# RJW_VCA.net
KiCad netlist of a schematic drawn in EAGLE
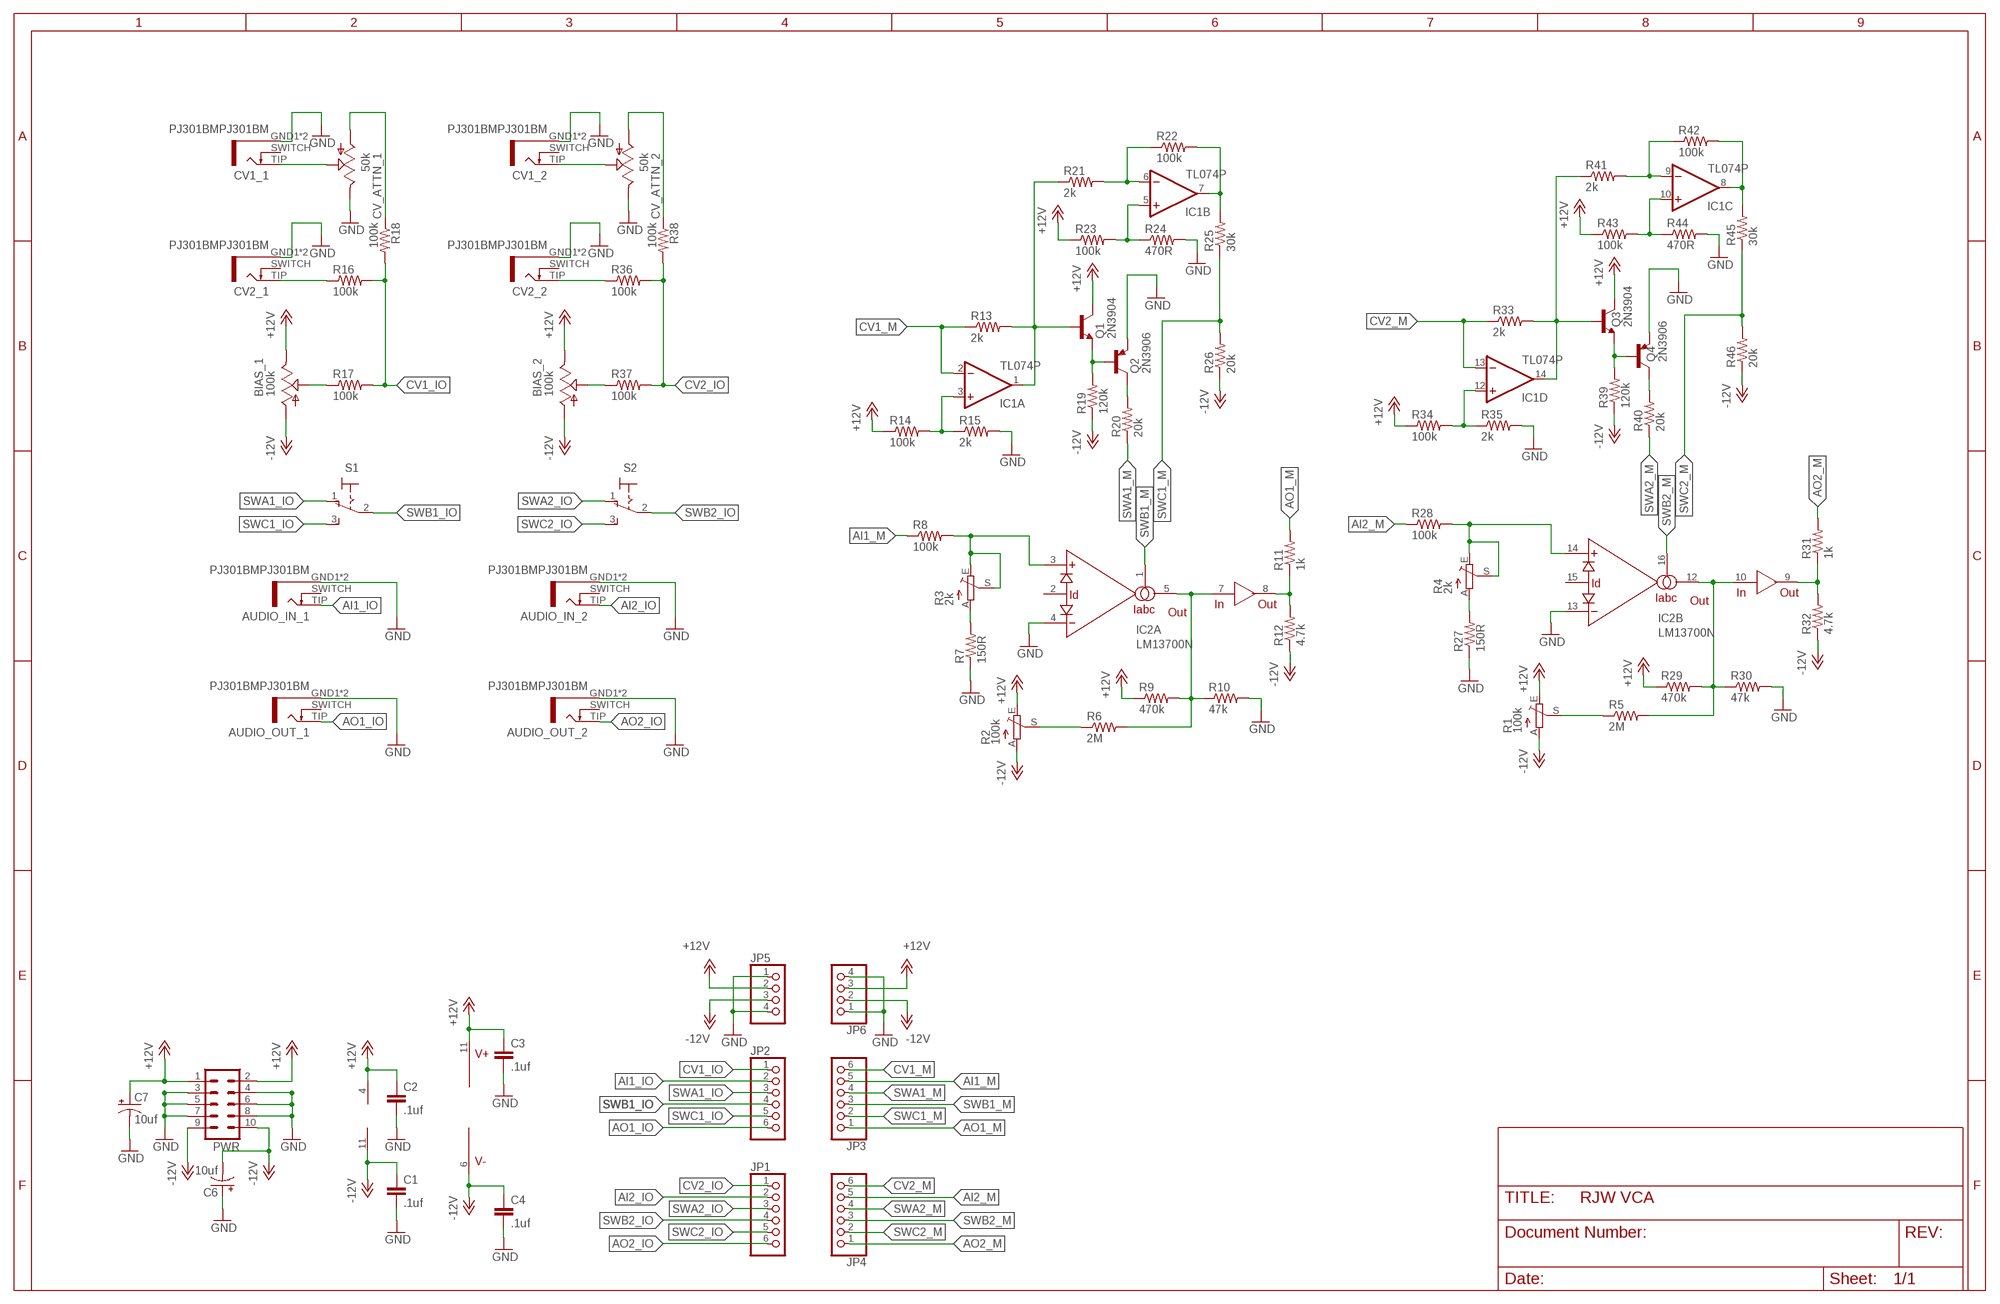
[diagram p0: schematic, sheet 1]

(export (version "E")
  (design (tool "Eeschema 10.0.6"))
  (components
    (comp (ref "AUDIO_IN_1")
      (value "PJ301BMPJ301BM")
      (footprint "eagle-import:PJ301BM")
      (libsource (lib "eagle-import") (part "PJ301BMPJ301BM"))
    )
    (comp (ref "AUDIO_IN_2")
      (value "PJ301BMPJ301BM")
      (footprint "eagle-import:PJ301BM")
      (libsource (lib "eagle-import") (part "PJ301BMPJ301BM"))
    )
    (comp (ref "AUDIO_OUT_1")
      (value "PJ301BMPJ301BM")
      (footprint "eagle-import:PJ301BM")
      (libsource (lib "eagle-import") (part "PJ301BMPJ301BM"))
    )
    (comp (ref "AUDIO_OUT_2")
      (value "PJ301BMPJ301BM")
      (footprint "eagle-import:PJ301BM")
      (libsource (lib "eagle-import") (part "PJ301BMPJ301BM"))
    )
    (comp (ref "BIAS_1")
      (value "100k")
      (footprint "eagle-import:EVUF")
      (libsource (lib "eagle-import") (part "ALPHA-9MMA"))
    )
    (comp (ref "BIAS_2")
      (value "100k")
      (footprint "eagle-import:EVUF")
      (libsource (lib "eagle-import") (part "ALPHA-9MMA"))
    )
    (comp (ref "C1")
      (value ".1uf")
      (footprint "eagle-import:C050-024X044")
      (libsource (lib "eagle-import") (part "C-EU050-024X044"))
    )
    (comp (ref "C2")
      (value ".1uf")
      (footprint "eagle-import:C050-024X044")
      (libsource (lib "eagle-import") (part "C-EU050-024X044"))
    )
    (comp (ref "C3")
      (value ".1uf")
      (footprint "eagle-import:C050-024X044")
      (libsource (lib "eagle-import") (part "C-EU050-024X044"))
    )
    (comp (ref "C4")
      (value ".1uf")
      (footprint "eagle-import:C050-024X044")
      (libsource (lib "eagle-import") (part "C-EU050-024X044"))
    )
    (comp (ref "C6")
      (value "10uf")
      (footprint "eagle-import:E2,5-5")
      (libsource (lib "eagle-import") (part "CPOL-USE2.5-5"))
    )
    (comp (ref "C7")
      (value "10uf")
      (footprint "eagle-import:E2,5-5")
      (libsource (lib "eagle-import") (part "CPOL-USE2.5-5"))
    )
    (comp (ref "CV1_1")
      (value "PJ301BMPJ301BM")
      (footprint "eagle-import:PJ301BM")
      (libsource (lib "eagle-import") (part "PJ301BMPJ301BM"))
    )
    (comp (ref "CV1_2")
      (value "PJ301BMPJ301BM")
      (footprint "eagle-import:PJ301BM")
      (libsource (lib "eagle-import") (part "PJ301BMPJ301BM"))
    )
    (comp (ref "CV2_1")
      (value "PJ301BMPJ301BM")
      (footprint "eagle-import:PJ301BM")
      (libsource (lib "eagle-import") (part "PJ301BMPJ301BM"))
    )
    (comp (ref "CV2_2")
      (value "PJ301BMPJ301BM")
      (footprint "eagle-import:PJ301BM")
      (libsource (lib "eagle-import") (part "PJ301BMPJ301BM"))
    )
    (comp (ref "CV_ATTN_1")
      (value "50k")
      (footprint "eagle-import:EVUF")
      (libsource (lib "eagle-import") (part "ALPHA-9MMA"))
    )
    (comp (ref "CV_ATTN_2")
      (value "50k")
      (footprint "eagle-import:EVUF")
      (libsource (lib "eagle-import") (part "ALPHA-9MMA"))
    )
    (comp (ref "IC1")
      (value "TL074P")
      (footprint "eagle-import:DIL14")
      (libsource (lib "eagle-import") (part "TL074P"))
    )
    (comp (ref "IC2")
      (value "LM13700N")
      (footprint "eagle-import:DIL16")
      (libsource (lib "eagle-import") (part "LM13700N"))
    )
    (comp (ref "JP1")
      (value "PINHD-1X6")
      (footprint "eagle-import:1X06")
      (libsource (lib "eagle-import") (part "PINHD-1X6"))
    )
    (comp (ref "JP2")
      (value "PINHD-1X6")
      (footprint "eagle-import:1X06")
      (libsource (lib "eagle-import") (part "PINHD-1X6"))
    )
    (comp (ref "JP3")
      (value "PINHD-1X6")
      (footprint "eagle-import:1X06")
      (libsource (lib "eagle-import") (part "PINHD-1X6"))
    )
    (comp (ref "JP4")
      (value "PINHD-1X6")
      (footprint "eagle-import:1X06")
      (libsource (lib "eagle-import") (part "PINHD-1X6"))
    )
    (comp (ref "JP5")
      (value "PINHD-1X4")
      (footprint "eagle-import:1X04")
      (libsource (lib "eagle-import") (part "PINHD-1X4"))
    )
    (comp (ref "JP6")
      (value "PINHD-1X4")
      (footprint "eagle-import:1X04")
      (libsource (lib "eagle-import") (part "PINHD-1X4"))
    )
    (comp (ref "PWR")
      (value "ML10")
      (footprint "eagle-import:ML10")
      (libsource (lib "eagle-import") (part "ML10"))
    )
    (comp (ref "Q1")
      (value "2N3904")
      (footprint "eagle-import:TO92")
      (libsource (lib "eagle-import") (part "2N3904"))
    )
    (comp (ref "Q2")
      (value "2N3906")
      (footprint "eagle-import:TO92")
      (libsource (lib "eagle-import") (part "2N3906"))
    )
    (comp (ref "Q3")
      (value "2N3904")
      (footprint "eagle-import:TO92")
      (libsource (lib "eagle-import") (part "2N3904"))
    )
    (comp (ref "Q4")
      (value "2N3906")
      (footprint "eagle-import:TO92")
      (libsource (lib "eagle-import") (part "2N3906"))
    )
    (comp (ref "R1")
      (value "100k")
      (footprint "eagle-import:S64YW")
      (libsource (lib "eagle-import") (part "TRIM_1234-S64YW"))
    )
    (comp (ref "R2")
      (value "100k")
      (footprint "eagle-import:S64YW")
      (libsource (lib "eagle-import") (part "TRIM_1234-S64YW"))
    )
    (comp (ref "R3")
      (value "2k")
      (footprint "eagle-import:S64YW")
      (libsource (lib "eagle-import") (part "TRIM_1234-S64YW"))
    )
    (comp (ref "R4")
      (value "2k")
      (footprint "eagle-import:S64YW")
      (libsource (lib "eagle-import") (part "TRIM_1234-S64YW"))
    )
    (comp (ref "R5")
      (value "2M")
      (footprint "eagle-import:0204_7")
      (libsource (lib "eagle-import") (part "R-US_0204/7"))
    )
    (comp (ref "R6")
      (value "2M")
      (footprint "eagle-import:0204_7")
      (libsource (lib "eagle-import") (part "R-US_0204/7"))
    )
    (comp (ref "R7")
      (value "150R")
      (footprint "eagle-import:0204_7")
      (libsource (lib "eagle-import") (part "R-US_0204/7"))
    )
    (comp (ref "R8")
      (value "100k")
      (footprint "eagle-import:0204_7")
      (libsource (lib "eagle-import") (part "R-US_0204/7"))
    )
    (comp (ref "R9")
      (value "470k")
      (footprint "eagle-import:0204_7")
      (libsource (lib "eagle-import") (part "R-US_0204/7"))
    )
    (comp (ref "R10")
      (value "47k")
      (footprint "eagle-import:0204_7")
      (libsource (lib "eagle-import") (part "R-US_0204/7"))
    )
    (comp (ref "R11")
      (value "1k")
      (footprint "eagle-import:0204_7")
      (libsource (lib "eagle-import") (part "R-US_0204/7"))
    )
    (comp (ref "R12")
      (value "4.7k")
      (footprint "eagle-import:0204_7")
      (libsource (lib "eagle-import") (part "R-US_0204/7"))
    )
    (comp (ref "R13")
      (value "2k")
      (footprint "eagle-import:0204_7")
      (libsource (lib "eagle-import") (part "R-US_0204/7"))
    )
    (comp (ref "R14")
      (value "100k")
      (footprint "eagle-import:0204_7")
      (libsource (lib "eagle-import") (part "R-US_0204/7"))
    )
    (comp (ref "R15")
      (value "2k")
      (footprint "eagle-import:0204_7")
      (libsource (lib "eagle-import") (part "R-US_0204/7"))
    )
    (comp (ref "R16")
      (value "100k")
      (footprint "eagle-import:0204_7")
      (libsource (lib "eagle-import") (part "R-US_0204/7"))
    )
    (comp (ref "R17")
      (value "100k")
      (footprint "eagle-import:0204_7")
      (libsource (lib "eagle-import") (part "R-US_0204/7"))
    )
    (comp (ref "R18")
      (value "100k")
      (footprint "eagle-import:0204_7")
      (libsource (lib "eagle-import") (part "R-US_0204/7"))
    )
    (comp (ref "R19")
      (value "120k")
      (footprint "eagle-import:0204_7")
      (libsource (lib "eagle-import") (part "R-US_0204/7"))
    )
    (comp (ref "R20")
      (value "20k")
      (footprint "eagle-import:0204_7")
      (libsource (lib "eagle-import") (part "R-US_0204/7"))
    )
    (comp (ref "R21")
      (value "2k")
      (footprint "eagle-import:0204_7")
      (libsource (lib "eagle-import") (part "R-US_0204/7"))
    )
    (comp (ref "R22")
      (value "100k")
      (footprint "eagle-import:0204_7")
      (libsource (lib "eagle-import") (part "R-US_0204/7"))
    )
    (comp (ref "R23")
      (value "100k")
      (footprint "eagle-import:0204_7")
      (libsource (lib "eagle-import") (part "R-US_0204/7"))
    )
    (comp (ref "R24")
      (value "470R")
      (footprint "eagle-import:0204_7")
      (libsource (lib "eagle-import") (part "R-US_0204/7"))
    )
    (comp (ref "R25")
      (value "30k")
      (footprint "eagle-import:0204_7")
      (libsource (lib "eagle-import") (part "R-US_0204/7"))
    )
    (comp (ref "R26")
      (value "20k")
      (footprint "eagle-import:0204_7")
      (libsource (lib "eagle-import") (part "R-US_0204/7"))
    )
    (comp (ref "R27")
      (value "150R")
      (footprint "eagle-import:0204_7")
      (libsource (lib "eagle-import") (part "R-US_0204/7"))
    )
    (comp (ref "R28")
      (value "100k")
      (footprint "eagle-import:0204_7")
      (libsource (lib "eagle-import") (part "R-US_0204/7"))
    )
    (comp (ref "R29")
      (value "470k")
      (footprint "eagle-import:0204_7")
      (libsource (lib "eagle-import") (part "R-US_0204/7"))
    )
    (comp (ref "R30")
      (value "47k")
      (footprint "eagle-import:0204_7")
      (libsource (lib "eagle-import") (part "R-US_0204/7"))
    )
    (comp (ref "R31")
      (value "1k")
      (footprint "eagle-import:0204_7")
      (libsource (lib "eagle-import") (part "R-US_0204/7"))
    )
    (comp (ref "R32")
      (value "4.7k")
      (footprint "eagle-import:0204_7")
      (libsource (lib "eagle-import") (part "R-US_0204/7"))
    )
    (comp (ref "R33")
      (value "2k")
      (footprint "eagle-import:0204_7")
      (libsource (lib "eagle-import") (part "R-US_0204/7"))
    )
    (comp (ref "R34")
      (value "100k")
      (footprint "eagle-import:0204_7")
      (libsource (lib "eagle-import") (part "R-US_0204/7"))
    )
    (comp (ref "R35")
      (value "2k")
      (footprint "eagle-import:0204_7")
      (libsource (lib "eagle-import") (part "R-US_0204/7"))
    )
    (comp (ref "R36")
      (value "100k")
      (footprint "eagle-import:0204_7")
      (libsource (lib "eagle-import") (part "R-US_0204/7"))
    )
    (comp (ref "R37")
      (value "100k")
      (footprint "eagle-import:0204_7")
      (libsource (lib "eagle-import") (part "R-US_0204/7"))
    )
    (comp (ref "R38")
      (value "100k")
      (footprint "eagle-import:0204_7")
      (libsource (lib "eagle-import") (part "R-US_0204/7"))
    )
    (comp (ref "R39")
      (value "120k")
      (footprint "eagle-import:0204_7")
      (libsource (lib "eagle-import") (part "R-US_0204/7"))
    )
    (comp (ref "R40")
      (value "20k")
      (footprint "eagle-import:0204_7")
      (libsource (lib "eagle-import") (part "R-US_0204/7"))
    )
    (comp (ref "R41")
      (value "2k")
      (footprint "eagle-import:0204_7")
      (libsource (lib "eagle-import") (part "R-US_0204/7"))
    )
    (comp (ref "R42")
      (value "100k")
      (footprint "eagle-import:0204_7")
      (libsource (lib "eagle-import") (part "R-US_0204/7"))
    )
    (comp (ref "R43")
      (value "100k")
      (footprint "eagle-import:0204_7")
      (libsource (lib "eagle-import") (part "R-US_0204/7"))
    )
    (comp (ref "R44")
      (value "470R")
      (footprint "eagle-import:0204_7")
      (libsource (lib "eagle-import") (part "R-US_0204/7"))
    )
    (comp (ref "R45")
      (value "30k")
      (footprint "eagle-import:0204_7")
      (libsource (lib "eagle-import") (part "R-US_0204/7"))
    )
    (comp (ref "R46")
      (value "20k")
      (footprint "eagle-import:0204_7")
      (libsource (lib "eagle-import") (part "R-US_0204/7"))
    )
    (comp (ref "S1")
      (value "M9040P")
      (footprint "eagle-import:M9040P")
      (libsource (lib "eagle-import") (part "M9040P"))
    )
    (comp (ref "S2")
      (value "M9040P")
      (footprint "eagle-import:M9040P")
      (libsource (lib "eagle-import") (part "M9040P"))
    )
  )
  (nets
    (net (code "1") (name "+12V") (class "Default")
      (node (ref "BIAS_1") (pin "3") (pinfunction "E_3") (pintype "passive"))
      (node (ref "BIAS_2") (pin "3") (pinfunction "E_3") (pintype "passive"))
      (node (ref "C2") (pin "1") (pinfunction "1_1") (pintype "passive"))
      (node (ref "C3") (pin "1") (pinfunction "1_1") (pintype "passive"))
      (node (ref "C7") (pin "+") (pinfunction "+_+") (pintype "passive"))
      (node (ref "IC1") (pin "4") (pinfunction "V+_4") (pintype "power_in"))
      (node (ref "IC2") (pin "11") (pinfunction "V+_11") (pintype "bidirectional"))
      (node (ref "JP5") (pin "2") (pinfunction "2_2") (pintype "passive"))
      (node (ref "JP6") (pin "3") (pinfunction "3_3") (pintype "passive"))
      (node (ref "PWR") (pin "1") (pinfunction "1_1") (pintype "passive"))
      (node (ref "PWR") (pin "2") (pinfunction "2_2") (pintype "passive"))
      (node (ref "Q1") (pin "1") (pinfunction "C_1") (pintype "passive"))
      (node (ref "Q3") (pin "1") (pinfunction "C_1") (pintype "passive"))
      (node (ref "R1") (pin "E") (pinfunction "E_E") (pintype "passive"))
      (node (ref "R14") (pin "1") (pinfunction "1_1") (pintype "passive"))
      (node (ref "R2") (pin "E") (pinfunction "E_E") (pintype "passive"))
      (node (ref "R23") (pin "1") (pinfunction "1_1") (pintype "passive"))
      (node (ref "R29") (pin "1") (pinfunction "1_1") (pintype "passive"))
      (node (ref "R34") (pin "1") (pinfunction "1_1") (pintype "passive"))
      (node (ref "R43") (pin "1") (pinfunction "1_1") (pintype "passive"))
      (node (ref "R9") (pin "1") (pinfunction "1_1") (pintype "passive"))
    )
    (net (code "2") (name "-12V") (class "Default")
      (node (ref "BIAS_1") (pin "1") (pinfunction "A_1") (pintype "passive"))
      (node (ref "BIAS_2") (pin "1") (pinfunction "A_1") (pintype "passive"))
      (node (ref "C1") (pin "1") (pinfunction "1_1") (pintype "passive"))
      (node (ref "C4") (pin "1") (pinfunction "1_1") (pintype "passive"))
      (node (ref "C6") (pin "-") (pinfunction "-_-") (pintype "passive"))
      (node (ref "IC1") (pin "11") (pinfunction "V-_11") (pintype "power_in"))
      (node (ref "IC2") (pin "6") (pinfunction "V-_6") (pintype "bidirectional"))
      (node (ref "JP5") (pin "3") (pinfunction "3_3") (pintype "passive"))
      (node (ref "JP6") (pin "2") (pinfunction "2_2") (pintype "passive"))
      (node (ref "PWR") (pin "10") (pinfunction "10_10") (pintype "passive"))
      (node (ref "PWR") (pin "9") (pinfunction "9_9") (pintype "passive"))
      (node (ref "R1") (pin "A") (pinfunction "A_A") (pintype "passive"))
      (node (ref "R12") (pin "1") (pinfunction "1_1") (pintype "passive"))
      (node (ref "R19") (pin "1") (pinfunction "1_1") (pintype "passive"))
      (node (ref "R2") (pin "A") (pinfunction "A_A") (pintype "passive"))
      (node (ref "R26") (pin "1") (pinfunction "1_1") (pintype "passive"))
      (node (ref "R32") (pin "1") (pinfunction "1_1") (pintype "passive"))
      (node (ref "R39") (pin "1") (pinfunction "1_1") (pintype "passive"))
      (node (ref "R46") (pin "1") (pinfunction "1_1") (pintype "passive"))
    )
    (net (code "3") (name "AI1_IO") (class "Default")
      (node (ref "AUDIO_IN_1") (pin "TIP") (pinfunction "3_TIP") (pintype "passive"))
      (node (ref "JP2") (pin "2") (pinfunction "2_2") (pintype "passive"))
    )
    (net (code "4") (name "AI1_M") (class "Default")
      (node (ref "JP3") (pin "5") (pinfunction "5_5") (pintype "passive"))
      (node (ref "R8") (pin "1") (pinfunction "1_1") (pintype "passive"))
    )
    (net (code "5") (name "AI2_IO") (class "Default")
      (node (ref "AUDIO_IN_2") (pin "TIP") (pinfunction "3_TIP") (pintype "passive"))
      (node (ref "JP1") (pin "2") (pinfunction "2_2") (pintype "passive"))
    )
    (net (code "6") (name "AI2_M") (class "Default")
      (node (ref "JP4") (pin "5") (pinfunction "5_5") (pintype "passive"))
      (node (ref "R28") (pin "1") (pinfunction "1_1") (pintype "passive"))
    )
    (net (code "7") (name "AO1_IO") (class "Default")
      (node (ref "AUDIO_OUT_1") (pin "TIP") (pinfunction "3_TIP") (pintype "passive"))
      (node (ref "JP2") (pin "6") (pinfunction "6_6") (pintype "passive"))
    )
    (net (code "8") (name "AO1_M") (class "Default")
      (node (ref "JP3") (pin "1") (pinfunction "1_1") (pintype "passive"))
      (node (ref "R11") (pin "2") (pinfunction "2_2") (pintype "passive"))
    )
    (net (code "9") (name "AO2_IO") (class "Default")
      (node (ref "AUDIO_OUT_2") (pin "TIP") (pinfunction "3_TIP") (pintype "passive"))
      (node (ref "JP1") (pin "6") (pinfunction "6_6") (pintype "passive"))
    )
    (net (code "10") (name "AO2_M") (class "Default")
      (node (ref "JP4") (pin "1") (pinfunction "1_1") (pintype "passive"))
      (node (ref "R31") (pin "2") (pinfunction "2_2") (pintype "passive"))
    )
    (net (code "11") (name "CV1_IO") (class "Default")
      (node (ref "JP2") (pin "1") (pinfunction "1_1") (pintype "passive"))
      (node (ref "R16") (pin "2") (pinfunction "2_2") (pintype "passive"))
      (node (ref "R17") (pin "2") (pinfunction "2_2") (pintype "passive"))
      (node (ref "R18") (pin "2") (pinfunction "2_2") (pintype "passive"))
    )
    (net (code "12") (name "CV1_M") (class "Default")
      (node (ref "IC1") (pin "2") (pinfunction "-IN_2") (pintype "input"))
      (node (ref "JP3") (pin "6") (pinfunction "6_6") (pintype "passive"))
      (node (ref "R13") (pin "1") (pinfunction "1_1") (pintype "passive"))
    )
    (net (code "13") (name "CV2_IO") (class "Default")
      (node (ref "JP1") (pin "1") (pinfunction "1_1") (pintype "passive"))
      (node (ref "R36") (pin "2") (pinfunction "2_2") (pintype "passive"))
      (node (ref "R37") (pin "2") (pinfunction "2_2") (pintype "passive"))
      (node (ref "R38") (pin "2") (pinfunction "2_2") (pintype "passive"))
    )
    (net (code "14") (name "CV2_M") (class "Default")
      (node (ref "IC1") (pin "13") (pinfunction "-IN_13") (pintype "input"))
      (node (ref "JP4") (pin "6") (pinfunction "6_6") (pintype "passive"))
      (node (ref "R33") (pin "1") (pinfunction "1_1") (pintype "passive"))
    )
    (net (code "15") (name "GND") (class "Default")
      (node (ref "AUDIO_IN_1") (pin "GND1") (pinfunction "5_GND1") (pintype "passive"))
      (node (ref "AUDIO_IN_1") (pin "GND2") (pinfunction "5_GND2") (pintype "passive"))
      (node (ref "AUDIO_IN_2") (pin "GND1") (pinfunction "5_GND1") (pintype "passive"))
      (node (ref "AUDIO_IN_2") (pin "GND2") (pinfunction "5_GND2") (pintype "passive"))
      (node (ref "AUDIO_OUT_1") (pin "GND1") (pinfunction "5_GND1") (pintype "passive"))
      (node (ref "AUDIO_OUT_1") (pin "GND2") (pinfunction "5_GND2") (pintype "passive"))
      (node (ref "AUDIO_OUT_2") (pin "GND1") (pinfunction "5_GND1") (pintype "passive"))
      (node (ref "AUDIO_OUT_2") (pin "GND2") (pinfunction "5_GND2") (pintype "passive"))
      (node (ref "C1") (pin "2") (pinfunction "2_2") (pintype "passive"))
      (node (ref "C2") (pin "2") (pinfunction "2_2") (pintype "passive"))
      (node (ref "C3") (pin "2") (pinfunction "2_2") (pintype "passive"))
      (node (ref "C4") (pin "2") (pinfunction "2_2") (pintype "passive"))
      (node (ref "C6") (pin "+") (pinfunction "+_+") (pintype "passive"))
      (node (ref "C7") (pin "-") (pinfunction "-_-") (pintype "passive"))
      (node (ref "CV1_1") (pin "GND1") (pinfunction "5_GND1") (pintype "passive"))
      (node (ref "CV1_1") (pin "GND2") (pinfunction "5_GND2") (pintype "passive"))
      (node (ref "CV1_2") (pin "GND1") (pinfunction "5_GND1") (pintype "passive"))
      (node (ref "CV1_2") (pin "GND2") (pinfunction "5_GND2") (pintype "passive"))
      (node (ref "CV2_1") (pin "GND1") (pinfunction "5_GND1") (pintype "passive"))
      (node (ref "CV2_1") (pin "GND2") (pinfunction "5_GND2") (pintype "passive"))
      (node (ref "CV2_2") (pin "GND1") (pinfunction "5_GND1") (pintype "passive"))
      (node (ref "CV2_2") (pin "GND2") (pinfunction "5_GND2") (pintype "passive"))
      (node (ref "CV_ATTN_1") (pin "3") (pinfunction "E_3") (pintype "passive"))
      (node (ref "CV_ATTN_2") (pin "3") (pinfunction "E_3") (pintype "passive"))
      (node (ref "IC2") (pin "13") (pinfunction "-IN_13") (pintype "bidirectional"))
      (node (ref "IC2") (pin "4") (pinfunction "-IN_4") (pintype "bidirectional"))
      (node (ref "JP5") (pin "1") (pinfunction "1_1") (pintype "passive"))
      (node (ref "JP5") (pin "4") (pinfunction "4_4") (pintype "passive"))
      (node (ref "JP6") (pin "1") (pinfunction "1_1") (pintype "passive"))
      (node (ref "JP6") (pin "4") (pinfunction "4_4") (pintype "passive"))
      (node (ref "PWR") (pin "3") (pinfunction "3_3") (pintype "passive"))
      (node (ref "PWR") (pin "4") (pinfunction "4_4") (pintype "passive"))
      (node (ref "PWR") (pin "5") (pinfunction "5_5") (pintype "passive"))
      (node (ref "PWR") (pin "6") (pinfunction "6_6") (pintype "passive"))
      (node (ref "PWR") (pin "7") (pinfunction "7_7") (pintype "passive"))
      (node (ref "PWR") (pin "8") (pinfunction "8_8") (pintype "passive"))
      (node (ref "Q2") (pin "3") (pinfunction "E_3") (pintype "passive"))
      (node (ref "Q4") (pin "3") (pinfunction "E_3") (pintype "passive"))
      (node (ref "R10") (pin "2") (pinfunction "2_2") (pintype "passive"))
      (node (ref "R15") (pin "2") (pinfunction "2_2") (pintype "passive"))
      (node (ref "R24") (pin "2") (pinfunction "2_2") (pintype "passive"))
      (node (ref "R27") (pin "1") (pinfunction "1_1") (pintype "passive"))
      (node (ref "R30") (pin "2") (pinfunction "2_2") (pintype "passive"))
      (node (ref "R35") (pin "2") (pinfunction "2_2") (pintype "passive"))
      (node (ref "R44") (pin "2") (pinfunction "2_2") (pintype "passive"))
      (node (ref "R7") (pin "1") (pinfunction "1_1") (pintype "passive"))
    )
    (net (code "16") (name "Net-(BIAS_1-S)") (class "Default")
      (node (ref "BIAS_1") (pin "2") (pinfunction "S_2") (pintype "passive"))
      (node (ref "R17") (pin "1") (pinfunction "1_1") (pintype "passive"))
    )
    (net (code "17") (name "Net-(BIAS_2-S)") (class "Default")
      (node (ref "BIAS_2") (pin "2") (pinfunction "S_2") (pintype "passive"))
      (node (ref "R37") (pin "1") (pinfunction "1_1") (pintype "passive"))
    )
    (net (code "18") (name "Net-(CV1_1-3)") (class "Default")
      (node (ref "CV1_1") (pin "TIP") (pinfunction "3_TIP") (pintype "passive"))
      (node (ref "CV_ATTN_1") (pin "2") (pinfunction "S_2") (pintype "passive"))
    )
    (net (code "19") (name "Net-(CV1_2-3)") (class "Default")
      (node (ref "CV1_2") (pin "TIP") (pinfunction "3_TIP") (pintype "passive"))
      (node (ref "CV_ATTN_2") (pin "2") (pinfunction "S_2") (pintype "passive"))
    )
    (net (code "20") (name "Net-(CV2_1-3)") (class "Default")
      (node (ref "CV2_1") (pin "TIP") (pinfunction "3_TIP") (pintype "passive"))
      (node (ref "R16") (pin "1") (pinfunction "1_1") (pintype "passive"))
    )
    (net (code "21") (name "Net-(CV2_2-3)") (class "Default")
      (node (ref "CV2_2") (pin "TIP") (pinfunction "3_TIP") (pintype "passive"))
      (node (ref "R36") (pin "1") (pinfunction "1_1") (pintype "passive"))
    )
    (net (code "22") (name "Net-(CV_ATTN_1-A)") (class "Default")
      (node (ref "CV_ATTN_1") (pin "1") (pinfunction "A_1") (pintype "passive"))
      (node (ref "R18") (pin "1") (pinfunction "1_1") (pintype "passive"))
    )
    (net (code "23") (name "Net-(CV_ATTN_2-A)") (class "Default")
      (node (ref "CV_ATTN_2") (pin "1") (pinfunction "A_1") (pintype "passive"))
      (node (ref "R38") (pin "1") (pinfunction "1_1") (pintype "passive"))
    )
    (net (code "24") (name "Net-(IC1A-+IN)") (class "Default")
      (node (ref "IC1") (pin "3") (pinfunction "+IN_3") (pintype "input"))
      (node (ref "R14") (pin "2") (pinfunction "2_2") (pintype "passive"))
      (node (ref "R15") (pin "1") (pinfunction "1_1") (pintype "passive"))
    )
    (net (code "25") (name "Net-(IC1A-OUT)") (class "Default")
      (node (ref "IC1") (pin "1") (pinfunction "OUT_1") (pintype "output"))
      (node (ref "Q1") (pin "2") (pinfunction "B_2") (pintype "passive"))
      (node (ref "R13") (pin "2") (pinfunction "2_2") (pintype "passive"))
      (node (ref "R21") (pin "1") (pinfunction "1_1") (pintype "passive"))
    )
    (net (code "26") (name "Net-(IC1B-+IN)") (class "Default")
      (node (ref "IC1") (pin "5") (pinfunction "+IN_5") (pintype "input"))
      (node (ref "R23") (pin "2") (pinfunction "2_2") (pintype "passive"))
      (node (ref "R24") (pin "1") (pinfunction "1_1") (pintype "passive"))
    )
    (net (code "27") (name "Net-(IC1B--IN)") (class "Default")
      (node (ref "IC1") (pin "6") (pinfunction "-IN_6") (pintype "input"))
      (node (ref "R21") (pin "2") (pinfunction "2_2") (pintype "passive"))
      (node (ref "R22") (pin "1") (pinfunction "1_1") (pintype "passive"))
    )
    (net (code "28") (name "Net-(IC1B-OUT)") (class "Default")
      (node (ref "IC1") (pin "7") (pinfunction "OUT_7") (pintype "output"))
      (node (ref "R22") (pin "2") (pinfunction "2_2") (pintype "passive"))
      (node (ref "R25") (pin "2") (pinfunction "2_2") (pintype "passive"))
    )
    (net (code "29") (name "Net-(IC1C-+IN)") (class "Default")
      (node (ref "IC1") (pin "10") (pinfunction "+IN_10") (pintype "input"))
      (node (ref "R43") (pin "2") (pinfunction "2_2") (pintype "passive"))
      (node (ref "R44") (pin "1") (pinfunction "1_1") (pintype "passive"))
    )
    (net (code "30") (name "Net-(IC1C--IN)") (class "Default")
      (node (ref "IC1") (pin "9") (pinfunction "-IN_9") (pintype "input"))
      (node (ref "R41") (pin "2") (pinfunction "2_2") (pintype "passive"))
      (node (ref "R42") (pin "1") (pinfunction "1_1") (pintype "passive"))
    )
    (net (code "31") (name "Net-(IC1C-OUT)") (class "Default")
      (node (ref "IC1") (pin "8") (pinfunction "OUT_8") (pintype "output"))
      (node (ref "R42") (pin "2") (pinfunction "2_2") (pintype "passive"))
      (node (ref "R45") (pin "2") (pinfunction "2_2") (pintype "passive"))
    )
    (net (code "32") (name "Net-(IC1D-+IN)") (class "Default")
      (node (ref "IC1") (pin "12") (pinfunction "+IN_12") (pintype "input"))
      (node (ref "R34") (pin "2") (pinfunction "2_2") (pintype "passive"))
      (node (ref "R35") (pin "1") (pinfunction "1_1") (pintype "passive"))
    )
    (net (code "33") (name "Net-(IC1D-OUT)") (class "Default")
      (node (ref "IC1") (pin "14") (pinfunction "OUT_14") (pintype "output"))
      (node (ref "Q3") (pin "2") (pinfunction "B_2") (pintype "passive"))
      (node (ref "R33") (pin "2") (pinfunction "2_2") (pintype "passive"))
      (node (ref "R41") (pin "1") (pinfunction "1_1") (pintype "passive"))
    )
    (net (code "34") (name "Net-(IC2A-+IN)") (class "Default")
      (node (ref "IC2") (pin "3") (pinfunction "+IN_3") (pintype "bidirectional"))
      (node (ref "R3") (pin "E") (pinfunction "E_E") (pintype "passive"))
      (node (ref "R3") (pin "S") (pinfunction "S_S") (pintype "passive"))
      (node (ref "R8") (pin "2") (pinfunction "2_2") (pintype "passive"))
    )
    (net (code "35") (name "Net-(IC2A-OUT)") (class "Default")
      (node (ref "IC2") (pin "5") (pinfunction "OUT_5") (pintype "bidirectional"))
      (node (ref "IC2") (pin "7") (pinfunction "IN_7") (pintype "bidirectional"))
      (node (ref "R10") (pin "1") (pinfunction "1_1") (pintype "passive"))
      (node (ref "R6") (pin "2") (pinfunction "2_2") (pintype "passive"))
      (node (ref "R9") (pin "2") (pinfunction "2_2") (pintype "passive"))
    )
    (net (code "36") (name "Net-(IC2B-+IN)") (class "Default")
      (node (ref "IC2") (pin "14") (pinfunction "+IN_14") (pintype "bidirectional"))
      (node (ref "R28") (pin "2") (pinfunction "2_2") (pintype "passive"))
      (node (ref "R4") (pin "E") (pinfunction "E_E") (pintype "passive"))
      (node (ref "R4") (pin "S") (pinfunction "S_S") (pintype "passive"))
    )
    (net (code "37") (name "Net-(IC2B-OUT)") (class "Default")
      (node (ref "IC2") (pin "10") (pinfunction "IN_10") (pintype "bidirectional"))
      (node (ref "IC2") (pin "12") (pinfunction "OUT_12") (pintype "bidirectional"))
      (node (ref "R29") (pin "2") (pinfunction "2_2") (pintype "passive"))
      (node (ref "R30") (pin "1") (pinfunction "1_1") (pintype "passive"))
      (node (ref "R5") (pin "2") (pinfunction "2_2") (pintype "passive"))
    )
    (net (code "38") (name "Net-(IC2C-OUT)") (class "Default")
      (node (ref "IC2") (pin "8") (pinfunction "OUT_8") (pintype "bidirectional"))
      (node (ref "R11") (pin "1") (pinfunction "1_1") (pintype "passive"))
      (node (ref "R12") (pin "2") (pinfunction "2_2") (pintype "passive"))
    )
    (net (code "39") (name "Net-(IC2D-OUT)") (class "Default")
      (node (ref "IC2") (pin "9") (pinfunction "OUT_9") (pintype "bidirectional"))
      (node (ref "R31") (pin "1") (pinfunction "1_1") (pintype "passive"))
      (node (ref "R32") (pin "2") (pinfunction "2_2") (pintype "passive"))
    )
    (net (code "40") (name "Net-(Q1-E)") (class "Default")
      (node (ref "Q1") (pin "3") (pinfunction "E_3") (pintype "passive"))
      (node (ref "Q2") (pin "2") (pinfunction "B_2") (pintype "passive"))
      (node (ref "R19") (pin "2") (pinfunction "2_2") (pintype "passive"))
    )
    (net (code "41") (name "Net-(Q2-C)") (class "Default")
      (node (ref "Q2") (pin "1") (pinfunction "C_1") (pintype "passive"))
      (node (ref "R20") (pin "2") (pinfunction "2_2") (pintype "passive"))
    )
    (net (code "42") (name "Net-(Q3-E)") (class "Default")
      (node (ref "Q3") (pin "3") (pinfunction "E_3") (pintype "passive"))
      (node (ref "Q4") (pin "2") (pinfunction "B_2") (pintype "passive"))
      (node (ref "R39") (pin "2") (pinfunction "2_2") (pintype "passive"))
    )
    (net (code "43") (name "Net-(Q4-C)") (class "Default")
      (node (ref "Q4") (pin "1") (pinfunction "C_1") (pintype "passive"))
      (node (ref "R40") (pin "2") (pinfunction "2_2") (pintype "passive"))
    )
    (net (code "44") (name "Net-(R1-PadS)") (class "Default")
      (node (ref "R1") (pin "S") (pinfunction "S_S") (pintype "passive"))
      (node (ref "R5") (pin "1") (pinfunction "1_1") (pintype "passive"))
    )
    (net (code "45") (name "Net-(R2-PadS)") (class "Default")
      (node (ref "R2") (pin "S") (pinfunction "S_S") (pintype "passive"))
      (node (ref "R6") (pin "1") (pinfunction "1_1") (pintype "passive"))
    )
    (net (code "46") (name "Net-(R3-PadA)") (class "Default")
      (node (ref "R3") (pin "A") (pinfunction "A_A") (pintype "passive"))
      (node (ref "R7") (pin "2") (pinfunction "2_2") (pintype "passive"))
    )
    (net (code "47") (name "Net-(R27-Pad2)") (class "Default")
      (node (ref "R27") (pin "2") (pinfunction "2_2") (pintype "passive"))
      (node (ref "R4") (pin "A") (pinfunction "A_A") (pintype "passive"))
    )
    (net (code "48") (name "SWA1_IO") (class "Default")
      (node (ref "JP2") (pin "3") (pinfunction "3_3") (pintype "passive"))
      (node (ref "S1") (pin "1") (pinfunction "O_1") (pintype "passive"))
    )
    (net (code "49") (name "SWA1_M") (class "Default")
      (node (ref "JP3") (pin "4") (pinfunction "4_4") (pintype "passive"))
      (node (ref "R20") (pin "1") (pinfunction "1_1") (pintype "passive"))
    )
    (net (code "50") (name "SWA2_IO") (class "Default")
      (node (ref "JP1") (pin "3") (pinfunction "3_3") (pintype "passive"))
      (node (ref "S2") (pin "1") (pinfunction "O_1") (pintype "passive"))
    )
    (net (code "51") (name "SWA2_M") (class "Default")
      (node (ref "JP4") (pin "4") (pinfunction "4_4") (pintype "passive"))
      (node (ref "R40") (pin "1") (pinfunction "1_1") (pintype "passive"))
    )
    (net (code "52") (name "SWB1_IO") (class "Default")
      (node (ref "JP2") (pin "4") (pinfunction "4_4") (pintype "passive"))
      (node (ref "S1") (pin "2") (pinfunction "P_2") (pintype "passive"))
    )
    (net (code "53") (name "SWB1_M") (class "Default")
      (node (ref "IC2") (pin "1") (pinfunction "IABC_1") (pintype "bidirectional"))
      (node (ref "JP3") (pin "3") (pinfunction "3_3") (pintype "passive"))
    )
    (net (code "54") (name "SWB2_IO") (class "Default")
      (node (ref "JP1") (pin "4") (pinfunction "4_4") (pintype "passive"))
      (node (ref "S2") (pin "2") (pinfunction "P_2") (pintype "passive"))
    )
    (net (code "55") (name "SWB2_M") (class "Default")
      (node (ref "IC2") (pin "16") (pinfunction "IABC_16") (pintype "bidirectional"))
      (node (ref "JP4") (pin "3") (pinfunction "3_3") (pintype "passive"))
    )
    (net (code "56") (name "SWC1_IO") (class "Default")
      (node (ref "JP2") (pin "5") (pinfunction "5_5") (pintype "passive"))
      (node (ref "S1") (pin "3") (pinfunction "S_3") (pintype "passive"))
    )
    (net (code "57") (name "SWC1_M") (class "Default")
      (node (ref "JP3") (pin "2") (pinfunction "2_2") (pintype "passive"))
      (node (ref "R25") (pin "1") (pinfunction "1_1") (pintype "passive"))
      (node (ref "R26") (pin "2") (pinfunction "2_2") (pintype "passive"))
    )
    (net (code "58") (name "SWC2_IO") (class "Default")
      (node (ref "JP1") (pin "5") (pinfunction "5_5") (pintype "passive"))
      (node (ref "S2") (pin "3") (pinfunction "S_3") (pintype "passive"))
    )
    (net (code "59") (name "SWC2_M") (class "Default")
      (node (ref "JP4") (pin "2") (pinfunction "2_2") (pintype "passive"))
      (node (ref "R45") (pin "1") (pinfunction "1_1") (pintype "passive"))
      (node (ref "R46") (pin "2") (pinfunction "2_2") (pintype "passive"))
    )
    (net (code "60") (name "unconnected-(AUDIO_IN_1-4-PadSWITCH)") (class "Default")
      (node (ref "AUDIO_IN_1") (pin "SWITCH") (pinfunction "4_SWITCH") (pintype "passive"))
    )
    (net (code "61") (name "unconnected-(AUDIO_IN_2-4-PadSWITCH)") (class "Default")
      (node (ref "AUDIO_IN_2") (pin "SWITCH") (pinfunction "4_SWITCH") (pintype "passive"))
    )
    (net (code "62") (name "unconnected-(AUDIO_OUT_1-4-PadSWITCH)") (class "Default")
      (node (ref "AUDIO_OUT_1") (pin "SWITCH") (pinfunction "4_SWITCH") (pintype "passive"))
    )
    (net (code "63") (name "unconnected-(AUDIO_OUT_2-4-PadSWITCH)") (class "Default")
      (node (ref "AUDIO_OUT_2") (pin "SWITCH") (pinfunction "4_SWITCH") (pintype "passive"))
    )
    (net (code "64") (name "unconnected-(CV1_1-4-PadSWITCH)") (class "Default")
      (node (ref "CV1_1") (pin "SWITCH") (pinfunction "4_SWITCH") (pintype "passive"))
    )
    (net (code "65") (name "unconnected-(CV1_2-4-PadSWITCH)") (class "Default")
      (node (ref "CV1_2") (pin "SWITCH") (pinfunction "4_SWITCH") (pintype "passive"))
    )
    (net (code "66") (name "unconnected-(CV2_1-4-PadSWITCH)") (class "Default")
      (node (ref "CV2_1") (pin "SWITCH") (pinfunction "4_SWITCH") (pintype "passive"))
    )
    (net (code "67") (name "unconnected-(CV2_2-4-PadSWITCH)") (class "Default")
      (node (ref "CV2_2") (pin "SWITCH") (pinfunction "4_SWITCH") (pintype "passive"))
    )
    (net (code "68") (name "unconnected-(IC2A-ID-Pad2)") (class "Default")
      (node (ref "IC2") (pin "2") (pinfunction "ID_2") (pintype "bidirectional"))
    )
    (net (code "69") (name "unconnected-(IC2B-ID-Pad15)") (class "Default")
      (node (ref "IC2") (pin "15") (pinfunction "ID_15") (pintype "bidirectional"))
    )
    (net (code "70") (name "unconnected-(R1-S-PadS@1)") (class "Default")
      (node (ref "R1") (pin "S@1") (pinfunction "S_S@1") (pintype "passive"))
    )
    (net (code "71") (name "unconnected-(R2-S-PadS@1)") (class "Default")
      (node (ref "R2") (pin "S@1") (pinfunction "S_S@1") (pintype "passive"))
    )
    (net (code "72") (name "unconnected-(R3-S-PadS@1)") (class "Default")
      (node (ref "R3") (pin "S@1") (pinfunction "S_S@1") (pintype "passive"))
    )
    (net (code "73") (name "unconnected-(R4-S-PadS@1)") (class "Default")
      (node (ref "R4") (pin "S@1") (pinfunction "S_S@1") (pintype "passive"))
    )
  )
)
